# bvm.net
KiCad netlist of a schematic drawn in EAGLE
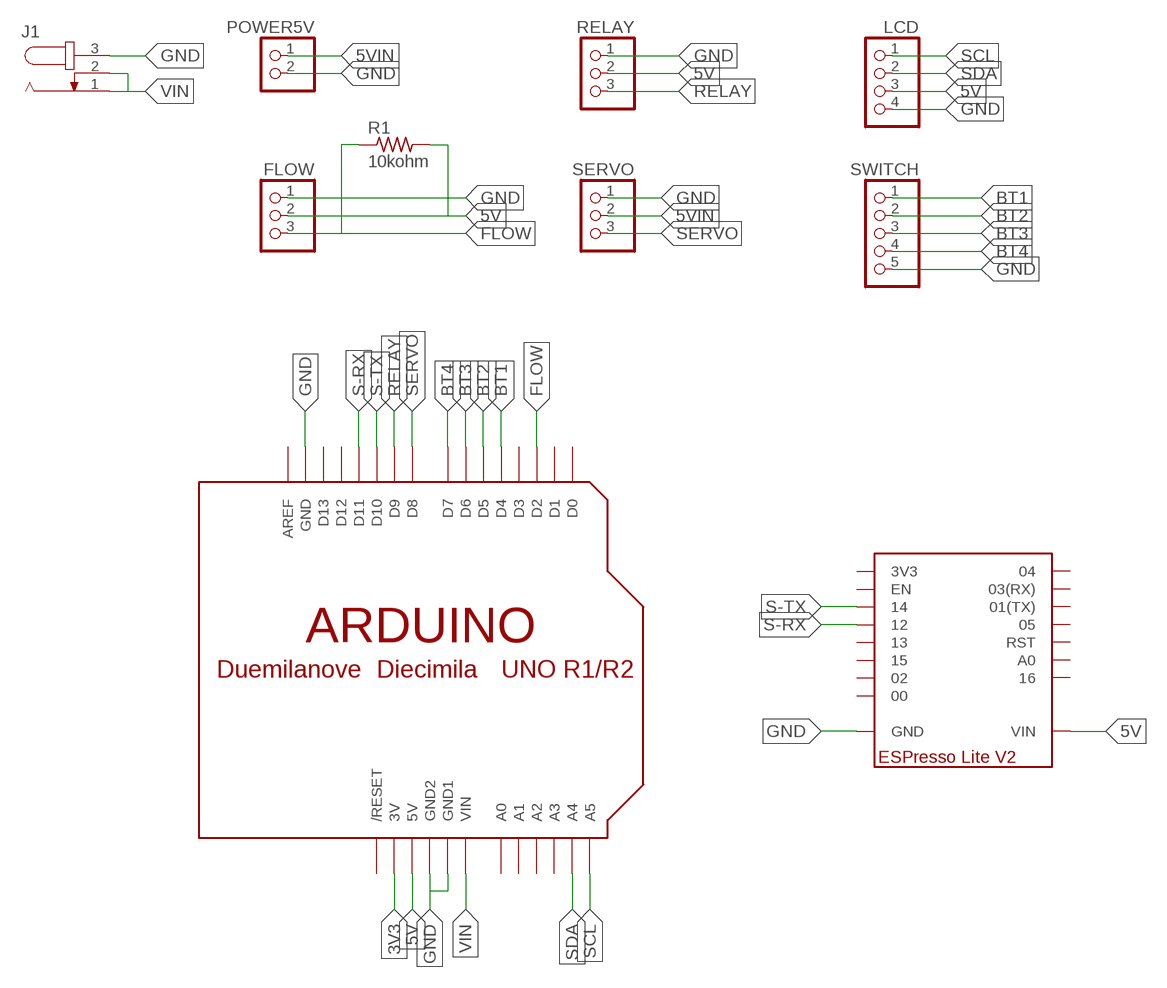
[diagram p0: schematic, sheet 1]

(export (version "E")
  (design (tool "Eeschema 10.0.6"))
  (components
    (comp (ref "FLOW")
      (value "PINHD-1X3")
      (footprint "eagle-import:1X03")
      (libsource (lib "eagle-import") (part "PINHD-1X3"))
    )
    (comp (ref "J1")
      (value "JACK-PLUG0")
      (footprint "eagle-import:SPC4077")
      (libsource (lib "eagle-import") (part "JACK-PLUG0"))
    )
    (comp (ref "LCD")
      (value "PINHD-1X4")
      (footprint "eagle-import:1X04")
      (libsource (lib "eagle-import") (part "PINHD-1X4"))
    )
    (comp (ref "POWER5V")
      (value "PINHD-1X2")
      (footprint "eagle-import:1X02")
      (libsource (lib "eagle-import") (part "PINHD-1X2"))
    )
    (comp (ref "R1")
      (value "10kohm")
      (footprint "eagle-import:0207_10")
      (libsource (lib "eagle-import") (part "R-US_0207/10"))
    )
    (comp (ref "RELAY")
      (value "PINHD-1X3")
      (footprint "eagle-import:1X03")
      (libsource (lib "eagle-import") (part "PINHD-1X3"))
    )
    (comp (ref "SERVO")
      (value "PINHD-1X3")
      (footprint "eagle-import:1X03")
      (libsource (lib "eagle-import") (part "PINHD-1X3"))
    )
    (comp (ref "SWITCH")
      (value "PINHD-1X5")
      (footprint "eagle-import:1X05")
      (libsource (lib "eagle-import") (part "PINHD-1X5"))
    )
    (comp (ref "U$1")
      (value "ARDUINOUNO")
      (footprint "eagle-import:ARDUINO")
      (libsource (lib "eagle-import") (part "ARDUINOUNO"))
    )
    (comp (ref "U$2")
      (value "ESPRESSO-LITE-V2")
      (footprint "eagle-import:ESPRESSO-LITE-V2")
      (libsource (lib "eagle-import") (part "ESPRESSO-LITE-V2"))
    )
  )
  (nets
    (net (code "1") (name "3V3") (class "Default")
      (node (ref "U$1") (pin "3V") (pinfunction "3V_3V") (pintype "power_in"))
    )
    (net (code "2") (name "5V") (class "Default")
      (node (ref "FLOW") (pin "2") (pinfunction "2_2") (pintype "passive"))
      (node (ref "LCD") (pin "3") (pinfunction "3_3") (pintype "passive"))
      (node (ref "R1") (pin "2") (pinfunction "2_2") (pintype "passive"))
      (node (ref "RELAY") (pin "2") (pinfunction "2_2") (pintype "passive"))
      (node (ref "U$1") (pin "5V") (pinfunction "5V_5V") (pintype "power_in"))
      (node (ref "U$2") (pin "VIN1") (pinfunction "VIN_VIN1") (pintype "bidirectional"))
      (node (ref "U$2") (pin "VIN2") (pinfunction "VIN_VIN2") (pintype "bidirectional"))
    )
    (net (code "3") (name "5VIN") (class "Default")
      (node (ref "POWER5V") (pin "1") (pinfunction "1_1") (pintype "passive"))
      (node (ref "SERVO") (pin "2") (pinfunction "2_2") (pintype "passive"))
    )
    (net (code "4") (name "BT1") (class "Default")
      (node (ref "SWITCH") (pin "1") (pinfunction "1_1") (pintype "passive"))
      (node (ref "U$1") (pin "D4") (pinfunction "D4_D4") (pintype "bidirectional"))
    )
    (net (code "5") (name "BT2") (class "Default")
      (node (ref "SWITCH") (pin "2") (pinfunction "2_2") (pintype "passive"))
      (node (ref "U$1") (pin "D5") (pinfunction "D5_D5") (pintype "bidirectional"))
    )
    (net (code "6") (name "BT3") (class "Default")
      (node (ref "SWITCH") (pin "3") (pinfunction "3_3") (pintype "passive"))
      (node (ref "U$1") (pin "D6") (pinfunction "D6_D6") (pintype "bidirectional"))
    )
    (net (code "7") (name "BT4") (class "Default")
      (node (ref "SWITCH") (pin "4") (pinfunction "4_4") (pintype "passive"))
      (node (ref "U$1") (pin "D7") (pinfunction "D7_D7") (pintype "bidirectional"))
    )
    (net (code "8") (name "FLOW") (class "Default")
      (node (ref "FLOW") (pin "3") (pinfunction "3_3") (pintype "passive"))
      (node (ref "R1") (pin "1") (pinfunction "1_1") (pintype "passive"))
      (node (ref "U$1") (pin "D2") (pinfunction "D2_D2") (pintype "bidirectional"))
    )
    (net (code "9") (name "GND") (class "Default")
      (node (ref "FLOW") (pin "1") (pinfunction "1_1") (pintype "passive"))
      (node (ref "J1") (pin "3") (pinfunction "3_3") (pintype "passive"))
      (node (ref "LCD") (pin "4") (pinfunction "4_4") (pintype "passive"))
      (node (ref "POWER5V") (pin "2") (pinfunction "2_2") (pintype "passive"))
      (node (ref "RELAY") (pin "1") (pinfunction "1_1") (pintype "passive"))
      (node (ref "SERVO") (pin "1") (pinfunction "1_1") (pintype "passive"))
      (node (ref "SWITCH") (pin "5") (pinfunction "5_5") (pintype "passive"))
      (node (ref "U$1") (pin "GND") (pinfunction "GND_GND") (pintype "power_in"))
      (node (ref "U$1") (pin "GND1") (pinfunction "GND1_GND1") (pintype "power_in"))
      (node (ref "U$1") (pin "GND2") (pinfunction "GND2_GND2") (pintype "power_in"))
      (node (ref "U$2") (pin "GND1") (pinfunction "GND_GND1") (pintype "bidirectional"))
      (node (ref "U$2") (pin "GND2") (pinfunction "GND_GND2") (pintype "bidirectional"))
      (node (ref "U$2") (pin "GND3") (pinfunction "GND_GND3") (pintype "bidirectional"))
    )
    (net (code "10") (name "RELAY") (class "Default")
      (node (ref "RELAY") (pin "3") (pinfunction "3_3") (pintype "passive"))
      (node (ref "U$1") (pin "D9") (pinfunction "D9_D9") (pintype "bidirectional"))
    )
    (net (code "11") (name "S-RX") (class "Default")
      (node (ref "U$1") (pin "D11") (pinfunction "D11_D11") (pintype "bidirectional"))
      (node (ref "U$2") (pin "12") (pinfunction "12_12") (pintype "bidirectional"))
    )
    (net (code "12") (name "S-TX") (class "Default")
      (node (ref "U$1") (pin "D10") (pinfunction "D10_D10") (pintype "bidirectional"))
      (node (ref "U$2") (pin "14") (pinfunction "14_14") (pintype "bidirectional"))
    )
    (net (code "13") (name "SCL") (class "Default")
      (node (ref "LCD") (pin "1") (pinfunction "1_1") (pintype "passive"))
      (node (ref "U$1") (pin "A5") (pinfunction "A5_A5") (pintype "bidirectional"))
    )
    (net (code "14") (name "SDA") (class "Default")
      (node (ref "LCD") (pin "2") (pinfunction "2_2") (pintype "passive"))
      (node (ref "U$1") (pin "A4") (pinfunction "A4_A4") (pintype "bidirectional"))
    )
    (net (code "15") (name "SERVO") (class "Default")
      (node (ref "SERVO") (pin "3") (pinfunction "3_3") (pintype "passive"))
      (node (ref "U$1") (pin "D8") (pinfunction "D8_D8") (pintype "bidirectional"))
    )
    (net (code "16") (name "VIN") (class "Default")
      (node (ref "J1") (pin "1") (pinfunction "1_1") (pintype "passive"))
      (node (ref "J1") (pin "2") (pinfunction "2_2") (pintype "passive"))
      (node (ref "U$1") (pin "VIN") (pinfunction "VIN_VIN") (pintype "power_in"))
    )
    (net (code "17") (name "unconnected-(U$1-PadA0)") (class "Default")
      (node (ref "U$1") (pin "A0") (pinfunction "A0_A0") (pintype "bidirectional"))
    )
    (net (code "18") (name "unconnected-(U$1-PadA1)") (class "Default")
      (node (ref "U$1") (pin "A1") (pinfunction "A1_A1") (pintype "bidirectional"))
    )
    (net (code "19") (name "unconnected-(U$1-PadA2)") (class "Default")
      (node (ref "U$1") (pin "A2") (pinfunction "A2_A2") (pintype "bidirectional"))
    )
    (net (code "20") (name "unconnected-(U$1-PadA3)") (class "Default")
      (node (ref "U$1") (pin "A3") (pinfunction "A3_A3") (pintype "bidirectional"))
    )
    (net (code "21") (name "unconnected-(U$1-PadAREF)") (class "Default")
      (node (ref "U$1") (pin "AREF") (pinfunction "AREF_AREF") (pintype "bidirectional"))
    )
    (net (code "22") (name "unconnected-(U$1-PadD0)") (class "Default")
      (node (ref "U$1") (pin "D0") (pinfunction "D0_D0") (pintype "bidirectional"))
    )
    (net (code "23") (name "unconnected-(U$1-PadD1)") (class "Default")
      (node (ref "U$1") (pin "D1") (pinfunction "D1_D1") (pintype "bidirectional"))
    )
    (net (code "24") (name "unconnected-(U$1-PadD3)") (class "Default")
      (node (ref "U$1") (pin "D3") (pinfunction "D3_D3") (pintype "bidirectional"))
    )
    (net (code "25") (name "unconnected-(U$1-PadD12)") (class "Default")
      (node (ref "U$1") (pin "D12") (pinfunction "D12_D12") (pintype "bidirectional"))
    )
    (net (code "26") (name "unconnected-(U$1-PadD13)") (class "Default")
      (node (ref "U$1") (pin "D13") (pinfunction "D13_D13") (pintype "bidirectional"))
    )
    (net (code "27") (name "unconnected-(U$1-{slash}RESET-PadRESET)") (class "Default")
      (node (ref "U$1") (pin "RESET") (pinfunction "/RESET_RESET") (pintype "bidirectional"))
    )
    (net (code "28") (name "unconnected-(U$2-01(TX)-Pad01)") (class "Default")
      (node (ref "U$2") (pin "01") (pinfunction "01(TX)_01") (pintype "bidirectional"))
    )
    (net (code "29") (name "unconnected-(U$2-03(RX)-Pad03)") (class "Default")
      (node (ref "U$2") (pin "03") (pinfunction "03(RX)_03") (pintype "bidirectional"))
    )
    (net (code "30") (name "unconnected-(U$2-A0-PadAO)") (class "Default")
      (node (ref "U$2") (pin "AO") (pinfunction "A0_AO") (pintype "bidirectional"))
    )
    (net (code "31") (name "unconnected-(U$2-Pad00)") (class "Default")
      (node (ref "U$2") (pin "00") (pinfunction "00_00") (pintype "bidirectional"))
    )
    (net (code "32") (name "unconnected-(U$2-Pad02)") (class "Default")
      (node (ref "U$2") (pin "02") (pinfunction "02_02") (pintype "bidirectional"))
    )
    (net (code "33") (name "unconnected-(U$2-Pad3V3)") (class "Default")
      (node (ref "U$2") (pin "3V3") (pinfunction "3V3_3V3") (pintype "bidirectional"))
    )
    (net (code "34") (name "unconnected-(U$2-Pad04)") (class "Default")
      (node (ref "U$2") (pin "04") (pinfunction "04_04") (pintype "bidirectional"))
    )
    (net (code "35") (name "unconnected-(U$2-Pad05)") (class "Default")
      (node (ref "U$2") (pin "05") (pinfunction "05_05") (pintype "bidirectional"))
    )
    (net (code "36") (name "unconnected-(U$2-Pad13)") (class "Default")
      (node (ref "U$2") (pin "13") (pinfunction "13_13") (pintype "bidirectional"))
    )
    (net (code "37") (name "unconnected-(U$2-Pad15)") (class "Default")
      (node (ref "U$2") (pin "15") (pinfunction "15_15") (pintype "bidirectional"))
    )
    (net (code "38") (name "unconnected-(U$2-Pad16)") (class "Default")
      (node (ref "U$2") (pin "16") (pinfunction "16_16") (pintype "bidirectional"))
    )
    (net (code "39") (name "unconnected-(U$2-PadEN)") (class "Default")
      (node (ref "U$2") (pin "EN") (pinfunction "EN_EN") (pintype "bidirectional"))
    )
    (net (code "40") (name "unconnected-(U$2-PadRST)") (class "Default")
      (node (ref "U$2") (pin "RST") (pinfunction "RST_RST") (pintype "bidirectional"))
    )
  )
)
